# cSLIM-shield.net
KiCad netlist of a schematic drawn in Altium Designer
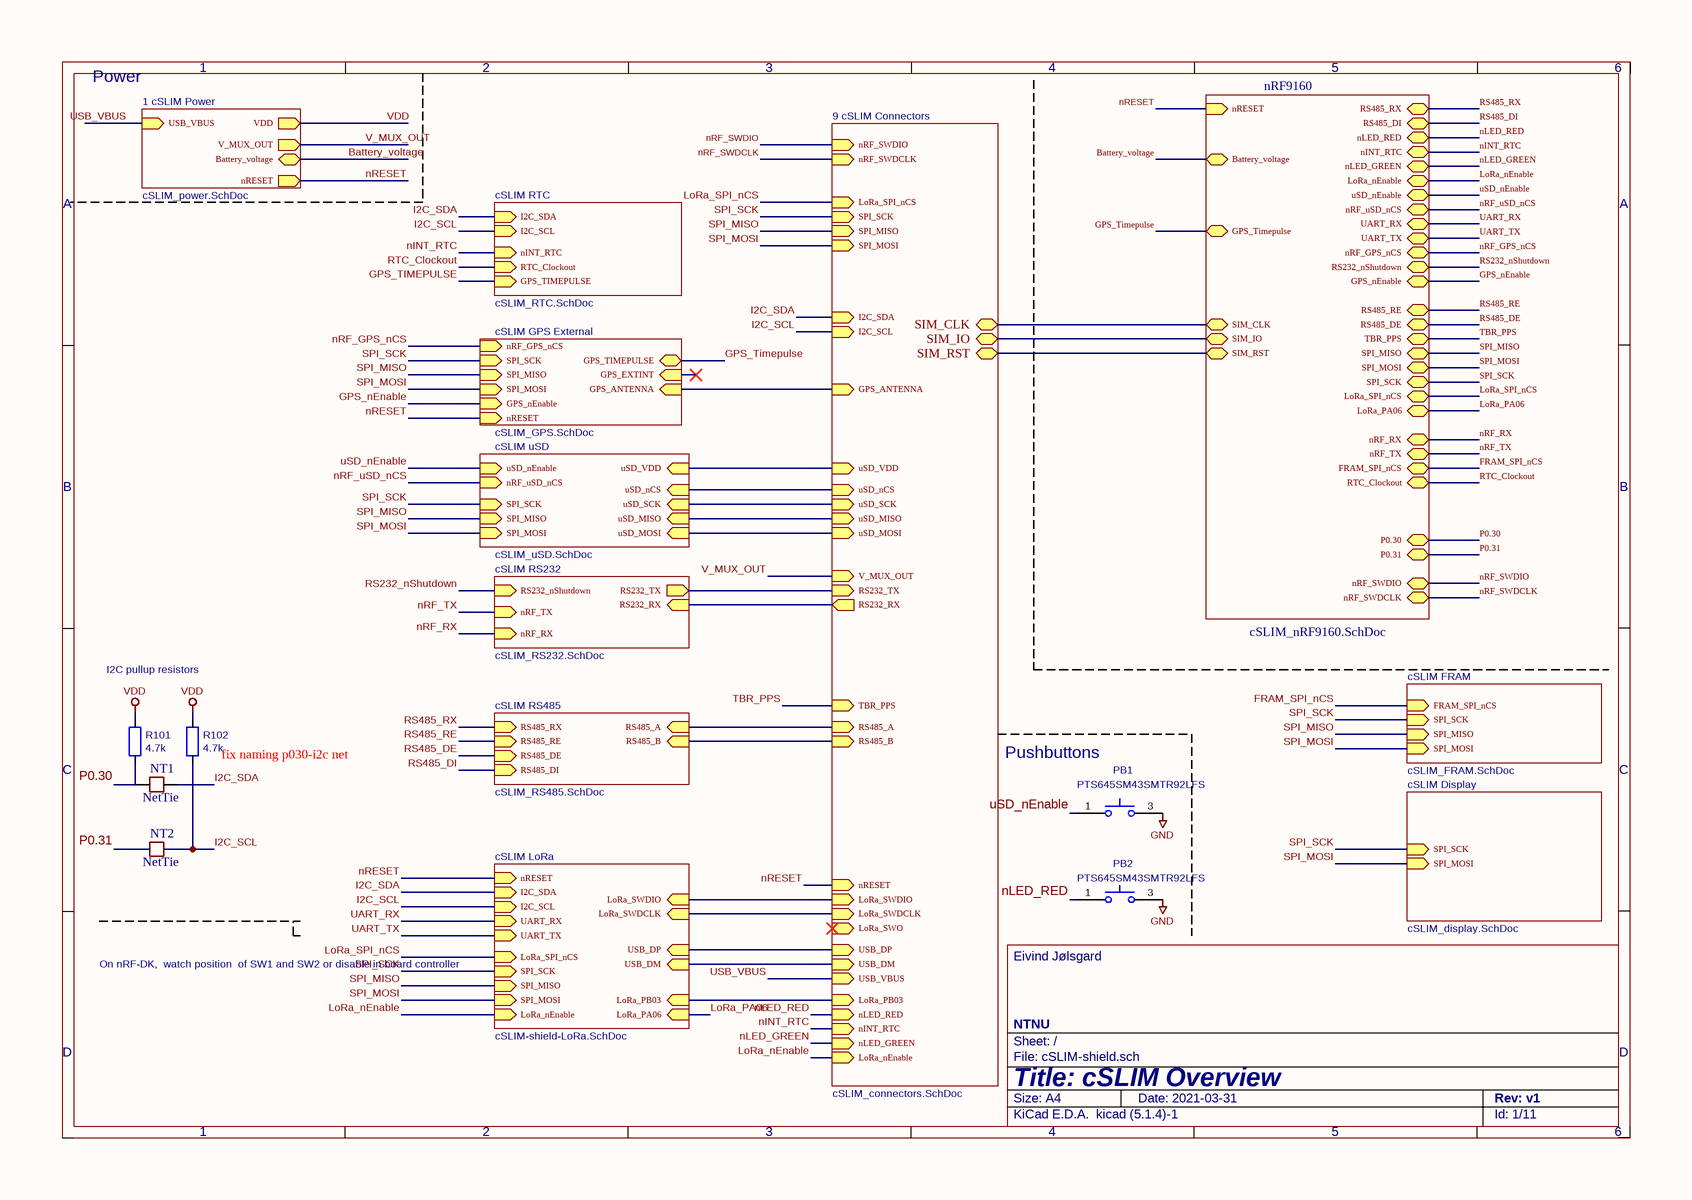
[diagram p0: cSLIM-shield.SchDoc]

(export (version "E")
  (design (tool "Eeschema 10.0.6"))
  (components
    (comp (ref "NT1") (value "NetTie") (footprint "NETTIE_FP") (libsource (lib "cSLIM-SA") (part "NetTie")))
    (comp (ref "NT2") (value "NetTie") (footprint "NETTIE_FP") (libsource (lib "cSLIM-SA") (part "NetTie")))
    (comp (ref "PB1")
      (value "PTS645SM43SMTR92LFS")
      (footprint "PTS645(SMT)")
      (description "Switch 4-pi. used 1-3 (2-4 not in use)")
      (fields
        (field (name "MOUSER PART NUMBER") "611-TLSA070JLFS")
        (field (name "MANUFACTURER_PART_NUMBER") "TLS A 070J LFS")
      )
      (libsource (lib "cSLIM-SA") (part "PTS645SM43SMTR92LFS"))
    )
    (comp (ref "PB2")
      (value "PTS645SM43SMTR92LFS")
      (footprint "PTS645(SMT)")
      (description "Switch 4-pi. used 1-3 (2-4 not in use)")
      (fields
        (field (name "MOUSER PART NUMBER") "611-TLSA070JLFS")
        (field (name "MANUFACTURER_PART_NUMBER") "TLS A 070J LFS")
      )
      (libsource (lib "cSLIM-SA") (part "PTS645SM43SMTR92LFS"))
    )
    (comp (ref "R101") (value "4.7k") (footprint "RESC1608X55N") (libsource (lib "cSLIM-SA") (part "R")))
    (comp (ref "R102") (value "4.7k") (footprint "RESC1608X55N") (libsource (lib "cSLIM-SA") (part "R")))
  )
  (nets
    (net (code "8") (name "/I2C_SCL") (class "Default")
      (node (ref "NT2") (pin "2") (pintype "passive"))
      (node (ref "R102") (pin "1") (pinfunction "1_1") (pintype "passive"))
    )
    (net (code "17") (name "/P0.30") (class "Default")
      (node (ref "R101") (pin "1") (pinfunction "1_1") (pintype "passive"))
    )
    (net (code "18") (name "/P0.31") (class "Default") (node (ref "NT2") (pin "1") (pintype "passive")))
    (net (code "44") (name "/nLED_RED") (class "Default")
      (node (ref "PB2") (pin "1") (pinfunction "1_1") (pintype "passive"))
    )
    (net (code "57") (name "/uSD_nEnable") (class "Default")
      (node (ref "PB1") (pin "1") (pinfunction "1_1") (pintype "passive"))
    )
    (net (code "58") (name "GND") (class "Default")
      (node (ref "PB1") (pin "3") (pinfunction "3_3") (pintype "passive"))
      (node (ref "PB2") (pin "3") (pinfunction "3_3") (pintype "passive"))
    )
    (net (code "59") (name "VDD") (class "Default")
      (node (ref "R101") (pin "2") (pinfunction "2_2") (pintype "passive"))
      (node (ref "R102") (pin "2") (pinfunction "2_2") (pintype "passive"))
    )
    (net (code "60") (name "unconnected-(NT1-Pad1)") (class "Default")
      (node (ref "NT1") (pin "1") (pintype "passive"))
    )
    (net (code "61") (name "unconnected-(NT1-Pad2)") (class "Default")
      (node (ref "NT1") (pin "2") (pintype "passive"))
    )
  )
)
